# Multimode-VCF-LM13600.net
KiCad netlist of a schematic drawn in EAGLE
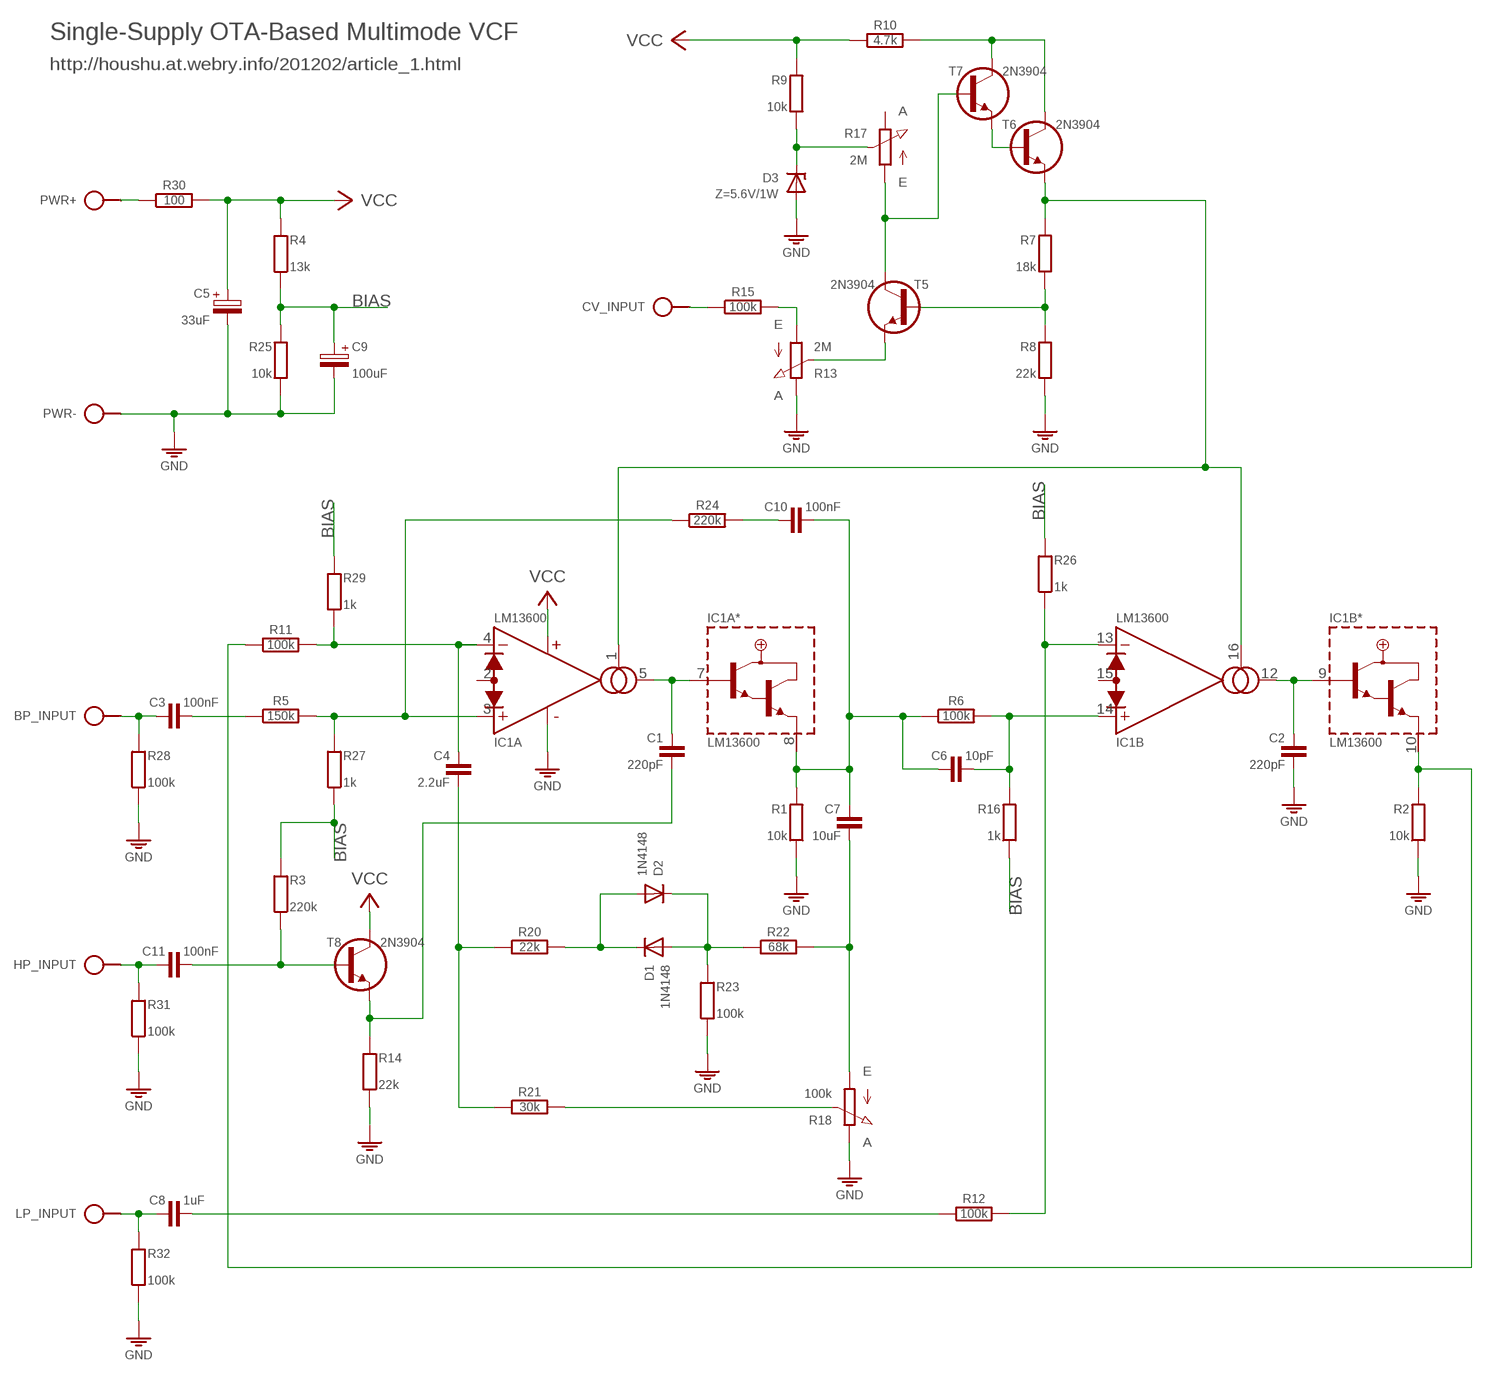
[diagram p0: schematic, sheet 1]

(export (version "E")
  (design (tool "Eeschema 10.0.6"))
  (components
    (comp (ref "BP_INPUT")
      (value "SPAD")
      (footprint "eagle-import:SPAD")
      (libsource (lib "eagle-import") (part "SPAD"))
    )
    (comp (ref "C1")
      (value "220pF")
      (footprint "eagle-import:C050-020X036_V")
      (libsource (lib "eagle-import") (part "C050-020X036/V"))
    )
    (comp (ref "C2")
      (value "220pF")
      (footprint "eagle-import:C050-020X036_V")
      (libsource (lib "eagle-import") (part "C050-020X036/V"))
    )
    (comp (ref "C3")
      (value "100nF")
      (footprint "eagle-import:C050-020X044")
      (libsource (lib "eagle-import") (part "C-H050-020X044"))
    )
    (comp (ref "C4")
      (value "2.2uF")
      (footprint "eagle-import:C050-024X044_V")
      (libsource (lib "eagle-import") (part "C050-024X044/V"))
    )
    (comp (ref "C5")
      (value "33uF")
      (footprint "eagle-import:E2.5-4_V")
      (libsource (lib "eagle-import") (part "CPOLE2,5-4/V"))
    )
    (comp (ref "C6")
      (value "10pF")
      (footprint "eagle-import:C050-020X036")
      (libsource (lib "eagle-import") (part "C-H050-020X036"))
    )
    (comp (ref "C7")
      (value "10uF")
      (footprint "eagle-import:C050-020X036_V")
      (libsource (lib "eagle-import") (part "C050-020X036/V"))
    )
    (comp (ref "C8")
      (value "1uF")
      (footprint "eagle-import:C050-024X044")
      (libsource (lib "eagle-import") (part "C-H050-024X044"))
    )
    (comp (ref "C9")
      (value "100uF")
      (footprint "eagle-import:E2.5-4_V")
      (libsource (lib "eagle-import") (part "CPOLE2,5-4/V"))
    )
    (comp (ref "C10")
      (value "100nF")
      (footprint "eagle-import:C050-020X044")
      (libsource (lib "eagle-import") (part "C-H050-020X044"))
    )
    (comp (ref "C11")
      (value "100nF")
      (footprint "eagle-import:C050-020X044_V")
      (libsource (lib "eagle-import") (part "C-H050-020X044/V"))
    )
    (comp (ref "CV_INPUT")
      (value "SPAD")
      (footprint "eagle-import:SPAD")
      (libsource (lib "eagle-import") (part "SPAD"))
    )
    (comp (ref "D1")
      (value "1N4148")
      (footprint "eagle-import:DO34-2,5-A")
      (libsource (lib "eagle-import") (part "1N414834-2,5-A"))
    )
    (comp (ref "D2")
      (value "1N4148")
      (footprint "eagle-import:DO34-2,5")
      (libsource (lib "eagle-import") (part "1N414834-2,5"))
    )
    (comp (ref "D3")
      (value "Z=5.6V/1W")
      (footprint "eagle-import:DO35Z7_V")
      (libsource (lib "eagle-import") (part "Z-DIODE-35Z7/V"))
    )
    (comp (ref "HP_INPUT")
      (value "SPAD")
      (footprint "eagle-import:SPAD")
      (libsource (lib "eagle-import") (part "SPAD"))
    )
    (comp (ref "IC1")
      (value "LM13600")
      (footprint "eagle-import:DIL16")
      (libsource (lib "eagle-import") (part "LM13600"))
    )
    (comp (ref "LP_INPUT")
      (value "SPAD")
      (footprint "eagle-import:SPAD")
      (libsource (lib "eagle-import") (part "SPAD"))
    )
    (comp (ref "PWR")
      (value "SPAD+--+")
      (footprint "eagle-import:SPAD-+")
      (libsource (lib "eagle-import") (part "SPAD+--+"))
    )
    (comp (ref "R1")
      (value "10k")
      (footprint "eagle-import:0204_10-V")
      (libsource (lib "eagle-import") (part "R0204/10-V"))
    )
    (comp (ref "R2")
      (value "10k")
      (footprint "eagle-import:0204_10")
      (libsource (lib "eagle-import") (part "R0204/10"))
    )
    (comp (ref "R3")
      (value "220k")
      (footprint "eagle-import:0204_10-V")
      (libsource (lib "eagle-import") (part "R0204/10-V"))
    )
    (comp (ref "R4")
      (value "13k")
      (footprint "eagle-import:0204_10-V")
      (libsource (lib "eagle-import") (part "R0204/10-V"))
    )
    (comp (ref "R5")
      (value "150k")
      (footprint "eagle-import:0204_10")
      (libsource (lib "eagle-import") (part "R-H0204/10"))
    )
    (comp (ref "R6")
      (value "100k")
      (footprint "eagle-import:0204_7-V")
      (libsource (lib "eagle-import") (part "R-H0204/7-V"))
    )
    (comp (ref "R7")
      (value "18k")
      (footprint "eagle-import:0204_10-V")
      (libsource (lib "eagle-import") (part "R0204/10-V"))
    )
    (comp (ref "R8")
      (value "22k")
      (footprint "eagle-import:0204_10-V")
      (libsource (lib "eagle-import") (part "R0204/10-V"))
    )
    (comp (ref "R9")
      (value "10k")
      (footprint "eagle-import:0204_10-V")
      (libsource (lib "eagle-import") (part "R0204/10-V"))
    )
    (comp (ref "R10")
      (value "4.7k")
      (footprint "eagle-import:0204_10")
      (libsource (lib "eagle-import") (part "R-H0204/10"))
    )
    (comp (ref "R11")
      (value "100k")
      (footprint "eagle-import:0204_10")
      (libsource (lib "eagle-import") (part "R-H0204/10"))
    )
    (comp (ref "R12")
      (value "100k")
      (footprint "eagle-import:0204_10")
      (libsource (lib "eagle-import") (part "R-H0204/10"))
    )
    (comp (ref "R13")
      (value "2M")
      (footprint "eagle-import:POT-V")
      (libsource (lib "eagle-import") (part "POT-V"))
    )
    (comp (ref "R14")
      (value "22k")
      (footprint "eagle-import:0204_10-V")
      (libsource (lib "eagle-import") (part "R0204/10-V"))
    )
    (comp (ref "R15")
      (value "100k")
      (footprint "eagle-import:0204_10")
      (libsource (lib "eagle-import") (part "R-H0204/10"))
    )
    (comp (ref "R16")
      (value "1k")
      (footprint "eagle-import:0204_7-V")
      (libsource (lib "eagle-import") (part "R0204/7-V"))
    )
    (comp (ref "R17")
      (value "2M")
      (footprint "eagle-import:POT-V")
      (libsource (lib "eagle-import") (part "POT-V"))
    )
    (comp (ref "R18")
      (value "100k")
      (footprint "eagle-import:POT")
      (libsource (lib "eagle-import") (part "POT"))
    )
    (comp (ref "R20")
      (value "22k")
      (footprint "eagle-import:0204_10")
      (libsource (lib "eagle-import") (part "R-H0204/10"))
    )
    (comp (ref "R21")
      (value "30k")
      (footprint "eagle-import:0204_10")
      (libsource (lib "eagle-import") (part "R-H0204/10"))
    )
    (comp (ref "R22")
      (value "68k")
      (footprint "eagle-import:0204_10")
      (libsource (lib "eagle-import") (part "R-H0204/10"))
    )
    (comp (ref "R23")
      (value "100k")
      (footprint "eagle-import:0204_10-V")
      (libsource (lib "eagle-import") (part "R0204/10-V"))
    )
    (comp (ref "R24")
      (value "220k")
      (footprint "eagle-import:0204_10-V")
      (libsource (lib "eagle-import") (part "R-H0204/10-V"))
    )
    (comp (ref "R25")
      (value "10k")
      (footprint "eagle-import:0204_10-V")
      (libsource (lib "eagle-import") (part "R0204/10-V"))
    )
    (comp (ref "R26")
      (value "1k")
      (footprint "eagle-import:0204_7")
      (libsource (lib "eagle-import") (part "R0204/7"))
    )
    (comp (ref "R27")
      (value "1k")
      (footprint "eagle-import:0204_10-V")
      (libsource (lib "eagle-import") (part "R0204/10-V"))
    )
    (comp (ref "R28")
      (value "100k")
      (footprint "eagle-import:0204_10-V")
      (libsource (lib "eagle-import") (part "R0204/10-V"))
    )
    (comp (ref "R29")
      (value "1k")
      (footprint "eagle-import:0204_10-V")
      (libsource (lib "eagle-import") (part "R0204/10-V"))
    )
    (comp (ref "R30")
      (value "100")
      (footprint "eagle-import:0204_10")
      (libsource (lib "eagle-import") (part "R-H0204/10"))
    )
    (comp (ref "R31")
      (value "100k")
      (footprint "eagle-import:0204_10-V")
      (libsource (lib "eagle-import") (part "R0204/10-V"))
    )
    (comp (ref "R32")
      (value "100k")
      (footprint "eagle-import:0204_10-V")
      (libsource (lib "eagle-import") (part "R0204/10-V"))
    )
    (comp (ref "T5")
      (value "2N3904")
      (footprint "eagle-import:TO92")
      (libsource (lib "eagle-import") (part "2N3904"))
    )
    (comp (ref "T6")
      (value "2N3904")
      (footprint "eagle-import:TO92")
      (libsource (lib "eagle-import") (part "2N3904"))
    )
    (comp (ref "T7")
      (value "2N3904")
      (footprint "eagle-import:TO92")
      (libsource (lib "eagle-import") (part "2N3904"))
    )
    (comp (ref "T8")
      (value "2N3904")
      (footprint "eagle-import:TO92")
      (libsource (lib "eagle-import") (part "2N3904"))
    )
  )
  (nets
    (net (code "1") (name "/BIAS") (class "Default")
      (node (ref "C9") (pin "+") (pinfunction "+_+") (pintype "passive"))
      (node (ref "R16") (pin "1") (pinfunction "2_1") (pintype "passive"))
      (node (ref "R25") (pin "1") (pinfunction "1_1") (pintype "passive"))
      (node (ref "R26") (pin "2") (pinfunction "1_2") (pintype "passive"))
      (node (ref "R27") (pin "2") (pinfunction "2_2") (pintype "passive"))
      (node (ref "R29") (pin "1") (pinfunction "1_1") (pintype "passive"))
      (node (ref "R3") (pin "1") (pinfunction "1_1") (pintype "passive"))
      (node (ref "R4") (pin "2") (pinfunction "2_2") (pintype "passive"))
    )
    (net (code "2") (name "GND") (class "Default")
      (node (ref "C2") (pin "2") (pinfunction "2_2") (pintype "passive"))
      (node (ref "C5") (pin "-") (pinfunction "-_-") (pintype "passive"))
      (node (ref "C9") (pin "-") (pinfunction "-_-") (pintype "passive"))
      (node (ref "D3") (pin "A") (pinfunction "A_A") (pintype "passive"))
      (node (ref "IC1") (pin "6") (pinfunction "V-_6") (pintype "power_in"))
      (node (ref "PWR") (pin "1") (pinfunction "P$1_1") (pintype "passive"))
      (node (ref "R1") (pin "2") (pinfunction "2_2") (pintype "passive"))
      (node (ref "R13") (pin "E") (pinfunction "E_E") (pintype "passive"))
      (node (ref "R14") (pin "2") (pinfunction "2_2") (pintype "passive"))
      (node (ref "R18") (pin "3") (pinfunction "E_3") (pintype "passive"))
      (node (ref "R2") (pin "1") (pinfunction "2_1") (pintype "passive"))
      (node (ref "R23") (pin "2") (pinfunction "2_2") (pintype "passive"))
      (node (ref "R25") (pin "2") (pinfunction "2_2") (pintype "passive"))
      (node (ref "R28") (pin "2") (pinfunction "2_2") (pintype "passive"))
      (node (ref "R31") (pin "2") (pinfunction "2_2") (pintype "passive"))
      (node (ref "R32") (pin "2") (pinfunction "2_2") (pintype "passive"))
      (node (ref "R8") (pin "2") (pinfunction "2_2") (pintype "passive"))
    )
    (net (code "3") (name "Net-(BP_INPUT-P$1)") (class "Default")
      (node (ref "BP_INPUT") (pin "1") (pinfunction "P$1_1") (pintype "passive"))
      (node (ref "C3") (pin "1") (pinfunction "1_1") (pintype "passive"))
      (node (ref "R28") (pin "1") (pinfunction "1_1") (pintype "passive"))
    )
    (net (code "4") (name "Net-(C3-Pad2)") (class "Default")
      (node (ref "C3") (pin "2") (pinfunction "2_2") (pintype "passive"))
      (node (ref "R5") (pin "1") (pinfunction "1_1") (pintype "passive"))
    )
    (net (code "5") (name "Net-(C4-Pad2)") (class "Default")
      (node (ref "C4") (pin "2") (pinfunction "2_2") (pintype "passive"))
      (node (ref "R20") (pin "1") (pinfunction "1_1") (pintype "passive"))
      (node (ref "R21") (pin "1") (pinfunction "1_1") (pintype "passive"))
    )
    (net (code "6") (name "Net-(C8-Pad2)") (class "Default")
      (node (ref "C8") (pin "2") (pinfunction "2_2") (pintype "passive"))
      (node (ref "R12") (pin "1") (pinfunction "1_1") (pintype "passive"))
    )
    (net (code "7") (name "Net-(C10-Pad1)") (class "Default")
      (node (ref "C10") (pin "1") (pinfunction "1_1") (pintype "passive"))
      (node (ref "R24") (pin "2") (pinfunction "2_2") (pintype "passive"))
    )
    (net (code "8") (name "Net-(CV_INPUT-P$1)") (class "Default")
      (node (ref "CV_INPUT") (pin "1") (pinfunction "P$1_1") (pintype "passive"))
      (node (ref "R15") (pin "1") (pinfunction "1_1") (pintype "passive"))
    )
    (net (code "9") (name "Net-(D1-PadA)") (class "Default")
      (node (ref "D1") (pin "A") (pinfunction "A_A") (pintype "passive"))
      (node (ref "D2") (pin "C") (pinfunction "C_C") (pintype "passive"))
      (node (ref "R22") (pin "1") (pinfunction "1_1") (pintype "passive"))
      (node (ref "R23") (pin "1") (pinfunction "1_1") (pintype "passive"))
    )
    (net (code "10") (name "Net-(D1-PadC)") (class "Default")
      (node (ref "D1") (pin "C") (pinfunction "C_C") (pintype "passive"))
      (node (ref "D2") (pin "A") (pinfunction "A_A") (pintype "passive"))
      (node (ref "R20") (pin "2") (pinfunction "2_2") (pintype "passive"))
    )
    (net (code "11") (name "Net-(D3-PadC)") (class "Default")
      (node (ref "D3") (pin "C") (pinfunction "C_C") (pintype "passive"))
      (node (ref "R17") (pin "S") (pinfunction "S_S") (pintype "passive"))
      (node (ref "R9") (pin "2") (pinfunction "2_2") (pintype "passive"))
    )
    (net (code "12") (name "Net-(HP_INPUT-P$1)") (class "Default")
      (node (ref "C11") (pin "1") (pinfunction "1_1") (pintype "passive"))
      (node (ref "HP_INPUT") (pin "1") (pinfunction "P$1_1") (pintype "passive"))
      (node (ref "R31") (pin "1") (pinfunction "1_1") (pintype "passive"))
    )
    (net (code "13") (name "Net-(IC1B-+IN)") (class "Default")
      (node (ref "IC1") (pin "3") (pinfunction "+IN_3") (pintype "input"))
      (node (ref "R24") (pin "1") (pinfunction "1_1") (pintype "passive"))
      (node (ref "R27") (pin "1") (pinfunction "1_1") (pintype "passive"))
      (node (ref "R5") (pin "2") (pinfunction "2_2") (pintype "passive"))
    )
    (net (code "14") (name "Net-(IC1B--IN)") (class "Default")
      (node (ref "C4") (pin "1") (pinfunction "1_1") (pintype "passive"))
      (node (ref "IC1") (pin "4") (pinfunction "-IN_4") (pintype "input"))
      (node (ref "R11") (pin "2") (pinfunction "2_2") (pintype "passive"))
      (node (ref "R29") (pin "2") (pinfunction "2_2") (pintype "passive"))
    )
    (net (code "15") (name "Net-(IC1B-AMP{slash}BIAS)") (class "Default")
      (node (ref "IC1") (pin "1") (pinfunction "AMP/BIAS_1") (pintype "input"))
      (node (ref "IC1") (pin "16") (pinfunction "AMP/BIAS_16") (pintype "input"))
      (node (ref "R7") (pin "1") (pinfunction "1_1") (pintype "passive"))
      (node (ref "T6") (pin "1") (pinfunction "E_1") (pintype "passive"))
    )
    (net (code "16") (name "Net-(IC1B-OUT)") (class "Default")
      (node (ref "C1") (pin "1") (pinfunction "1_1") (pintype "passive"))
      (node (ref "IC1") (pin "5") (pinfunction "OUT_5") (pintype "output"))
      (node (ref "IC1") (pin "7") (pinfunction "BUFF/IN_7") (pintype "input"))
    )
    (net (code "17") (name "Net-(IC1C-BUFF{slash}OUT)") (class "Default")
      (node (ref "C10") (pin "2") (pinfunction "2_2") (pintype "passive"))
      (node (ref "C6") (pin "1") (pinfunction "1_1") (pintype "passive"))
      (node (ref "C7") (pin "1") (pinfunction "1_1") (pintype "passive"))
      (node (ref "IC1") (pin "8") (pinfunction "BUFF/OUT_8") (pintype "output"))
      (node (ref "R1") (pin "1") (pinfunction "1_1") (pintype "passive"))
      (node (ref "R6") (pin "1") (pinfunction "1_1") (pintype "passive"))
    )
    (net (code "18") (name "Net-(IC1D-+IN)") (class "Default")
      (node (ref "C6") (pin "2") (pinfunction "2_2") (pintype "passive"))
      (node (ref "IC1") (pin "14") (pinfunction "+IN_14") (pintype "input"))
      (node (ref "R16") (pin "2") (pinfunction "1_2") (pintype "passive"))
      (node (ref "R6") (pin "2") (pinfunction "2_2") (pintype "passive"))
    )
    (net (code "19") (name "Net-(IC1D--IN)") (class "Default")
      (node (ref "IC1") (pin "13") (pinfunction "-IN_13") (pintype "input"))
      (node (ref "R12") (pin "2") (pinfunction "2_2") (pintype "passive"))
      (node (ref "R26") (pin "1") (pinfunction "2_1") (pintype "passive"))
    )
    (net (code "20") (name "Net-(IC1D-OUT)") (class "Default")
      (node (ref "C2") (pin "1") (pinfunction "1_1") (pintype "passive"))
      (node (ref "IC1") (pin "12") (pinfunction "OUT_12") (pintype "output"))
      (node (ref "IC1") (pin "9") (pinfunction "BUFF/IN_9") (pintype "input"))
    )
    (net (code "21") (name "Net-(IC1E-BUFF{slash}OUT)") (class "Default")
      (node (ref "IC1") (pin "10") (pinfunction "BUFF/OUT_10") (pintype "output"))
      (node (ref "R11") (pin "1") (pinfunction "1_1") (pintype "passive"))
      (node (ref "R2") (pin "2") (pinfunction "1_2") (pintype "passive"))
    )
    (net (code "22") (name "Net-(LP_INPUT-P$1)") (class "Default")
      (node (ref "C8") (pin "1") (pinfunction "1_1") (pintype "passive"))
      (node (ref "LP_INPUT") (pin "1") (pinfunction "P$1_1") (pintype "passive"))
      (node (ref "R32") (pin "1") (pinfunction "1_1") (pintype "passive"))
    )
    (net (code "23") (name "Net-(PWRA-P$1)") (class "Default")
      (node (ref "PWR") (pin "2") (pinfunction "P$1_2") (pintype "passive"))
      (node (ref "R30") (pin "1") (pinfunction "1_1") (pintype "passive"))
    )
    (net (code "24") (name "Net-(R13-PadA)") (class "Default")
      (node (ref "R13") (pin "A") (pinfunction "A_A") (pintype "passive"))
      (node (ref "R15") (pin "2") (pinfunction "2_2") (pintype "passive"))
    )
    (net (code "25") (name "Net-(R18-A)") (class "Default")
      (node (ref "C7") (pin "2") (pinfunction "2_2") (pintype "passive"))
      (node (ref "R18") (pin "1") (pinfunction "A_1") (pintype "passive"))
      (node (ref "R22") (pin "2") (pinfunction "2_2") (pintype "passive"))
    )
    (net (code "26") (name "Net-(R18-S)") (class "Default")
      (node (ref "R18") (pin "2") (pinfunction "S_2") (pintype "passive"))
      (node (ref "R21") (pin "2") (pinfunction "2_2") (pintype "passive"))
    )
    (net (code "27") (name "Net-(T5-B)") (class "Default")
      (node (ref "R7") (pin "2") (pinfunction "2_2") (pintype "passive"))
      (node (ref "R8") (pin "1") (pinfunction "1_1") (pintype "passive"))
      (node (ref "T5") (pin "2") (pinfunction "B_2") (pintype "passive"))
    )
    (net (code "28") (name "Net-(T5-C)") (class "Default")
      (node (ref "R17") (pin "A") (pinfunction "A_A") (pintype "passive"))
      (node (ref "T5") (pin "3") (pinfunction "C_3") (pintype "passive"))
      (node (ref "T7") (pin "2") (pinfunction "B_2") (pintype "passive"))
    )
    (net (code "29") (name "Net-(T5-E)") (class "Default")
      (node (ref "R13") (pin "S") (pinfunction "S_S") (pintype "passive"))
      (node (ref "T5") (pin "1") (pinfunction "E_1") (pintype "passive"))
    )
    (net (code "30") (name "Net-(T6-B)") (class "Default")
      (node (ref "T6") (pin "2") (pinfunction "B_2") (pintype "passive"))
      (node (ref "T7") (pin "1") (pinfunction "E_1") (pintype "passive"))
    )
    (net (code "31") (name "Net-(T6-C)") (class "Default")
      (node (ref "R10") (pin "2") (pinfunction "2_2") (pintype "passive"))
      (node (ref "T6") (pin "3") (pinfunction "C_3") (pintype "passive"))
      (node (ref "T7") (pin "3") (pinfunction "C_3") (pintype "passive"))
    )
    (net (code "32") (name "Net-(T8-B)") (class "Default")
      (node (ref "C11") (pin "2") (pinfunction "2_2") (pintype "passive"))
      (node (ref "R3") (pin "2") (pinfunction "2_2") (pintype "passive"))
      (node (ref "T8") (pin "2") (pinfunction "B_2") (pintype "passive"))
    )
    (net (code "33") (name "Net-(T8-E)") (class "Default")
      (node (ref "C1") (pin "2") (pinfunction "2_2") (pintype "passive"))
      (node (ref "R14") (pin "1") (pinfunction "1_1") (pintype "passive"))
      (node (ref "T8") (pin "1") (pinfunction "E_1") (pintype "passive"))
    )
    (net (code "34") (name "VCC") (class "Default")
      (node (ref "C5") (pin "+") (pinfunction "+_+") (pintype "passive"))
      (node (ref "IC1") (pin "11") (pinfunction "V+_11") (pintype "power_in"))
      (node (ref "R10") (pin "1") (pinfunction "1_1") (pintype "passive"))
      (node (ref "R30") (pin "2") (pinfunction "2_2") (pintype "passive"))
      (node (ref "R4") (pin "1") (pinfunction "1_1") (pintype "passive"))
      (node (ref "R9") (pin "1") (pinfunction "1_1") (pintype "passive"))
      (node (ref "T8") (pin "3") (pinfunction "C_3") (pintype "passive"))
    )
    (net (code "35") (name "unconnected-(IC1B-DIODE{slash}BIAS-Pad2)") (class "Default")
      (node (ref "IC1") (pin "2") (pinfunction "DIODE/BIAS_2") (pintype "passive"))
    )
    (net (code "36") (name "unconnected-(IC1D-DIODE{slash}BIAS-Pad15)") (class "Default")
      (node (ref "IC1") (pin "15") (pinfunction "DIODE/BIAS_15") (pintype "passive"))
    )
    (net (code "37") (name "unconnected-(R17-PadE)") (class "Default")
      (node (ref "R17") (pin "E") (pinfunction "E_E") (pintype "passive"))
    )
  )
)
